# interrupter.net
KiCad netlist of a schematic drawn in EAGLE
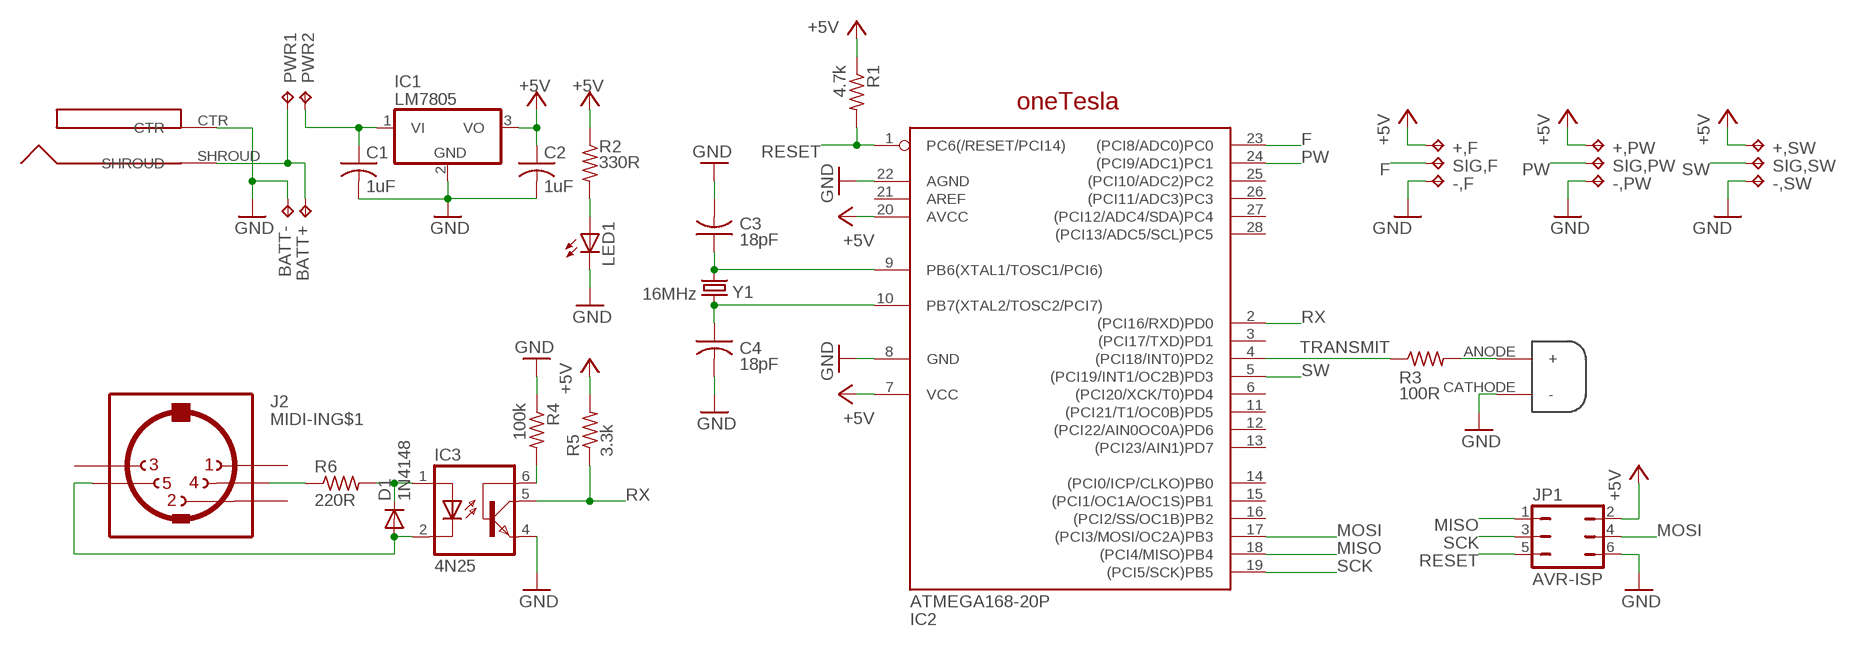
[diagram p0: schematic, sheet 1]

(export (version "E")
  (design (tool "Eeschema 10.0.6"))
  (components
    (comp (ref "+,F")
      (value "TPPAD1-13")
      (footprint "eagle-import:P1-13")
      (libsource (lib "eagle-import") (part "TPPAD1-13"))
    )
    (comp (ref "+,PW")
      (value "TPPAD1-13")
      (footprint "eagle-import:P1-13")
      (libsource (lib "eagle-import") (part "TPPAD1-13"))
    )
    (comp (ref "+,SW")
      (value "TPPAD1-13")
      (footprint "eagle-import:P1-13")
      (libsource (lib "eagle-import") (part "TPPAD1-13"))
    )
    (comp (ref "-,F")
      (value "TPPAD1-13")
      (footprint "eagle-import:P1-13")
      (libsource (lib "eagle-import") (part "TPPAD1-13"))
    )
    (comp (ref "-,PW")
      (value "TPPAD1-13")
      (footprint "eagle-import:P1-13")
      (libsource (lib "eagle-import") (part "TPPAD1-13"))
    )
    (comp (ref "-,SW")
      (value "TPPAD1-13")
      (footprint "eagle-import:P1-13")
      (libsource (lib "eagle-import") (part "TPPAD1-13"))
    )
    (comp (ref "BATT+")
      (value "TPPAD1-13")
      (footprint "eagle-import:P1-13")
      (libsource (lib "eagle-import") (part "TPPAD1-13"))
    )
    (comp (ref "BATT-")
      (value "TPPAD1-13")
      (footprint "eagle-import:P1-13")
      (libsource (lib "eagle-import") (part "TPPAD1-13"))
    )
    (comp (ref "C1")
      (value "1uF")
      (footprint "eagle-import:C050-024X044")
      (libsource (lib "eagle-import") (part "C-US050-024X044"))
    )
    (comp (ref "C2")
      (value "1uF")
      (footprint "eagle-import:C050-024X044")
      (libsource (lib "eagle-import") (part "C-US050-024X044"))
    )
    (comp (ref "C3")
      (value "18pF")
      (footprint "eagle-import:C025-024X044")
      (libsource (lib "eagle-import") (part "C-US025-024X044"))
    )
    (comp (ref "C4")
      (value "18pF")
      (footprint "eagle-import:C025-024X044")
      (libsource (lib "eagle-import") (part "C-US025-024X044"))
    )
    (comp (ref "D1")
      (value "1N4148")
      (footprint "eagle-import:DO35-7")
      (libsource (lib "eagle-import") (part "1N4148DO35-7"))
    )
    (comp (ref "IC1")
      (value "LM7805")
      (footprint "eagle-import:TO220H")
      (libsource (lib "eagle-import") (part "78T05"))
    )
    (comp (ref "IC2")
      (value "ATMEGA168-20P")
      (footprint "eagle-import:DIL28-3")
      (libsource (lib "eagle-import") (part "ATMEGA168P-20"))
    )
    (comp (ref "IC3")
      (value "4N25")
      (footprint "eagle-import:DIL06")
      (fields (field (name "MPN") "4N25-M"))
      (libsource (lib "eagle-import") (part "4N?M25"))
    )
    (comp (ref "JP1")
      (value "AVR-ISP")
      (footprint "eagle-import:JP3Q")
      (libsource (lib "eagle-import") (part "JP3Q"))
    )
    (comp (ref "LED1")
      (value "LED5MM")
      (footprint "eagle-import:LED5MM")
      (libsource (lib "eagle-import") (part "LED5MM"))
    )
    (comp (ref "MIDI-IN")
      (value "J2")
      (footprint "eagle-import:CP-2350")
      (libsource (lib "eagle-import") (part "MIDIJACK"))
    )
    (comp (ref "POWER")
      (value "J1")
      (footprint "eagle-import:DJC0202")
      (libsource (lib "eagle-import") (part "PJ-037B"))
    )
    (comp (ref "PWR1")
      (value "TPPAD1-13")
      (footprint "eagle-import:P1-13")
      (libsource (lib "eagle-import") (part "TPPAD1-13"))
    )
    (comp (ref "PWR2")
      (value "TPPAD1-13")
      (footprint "eagle-import:P1-13")
      (libsource (lib "eagle-import") (part "TPPAD1-13"))
    )
    (comp (ref "R1")
      (value "4.7k")
      (footprint "eagle-import:0207_7")
      (libsource (lib "eagle-import") (part "R-US_0207/7"))
    )
    (comp (ref "R2")
      (value "330R")
      (footprint "eagle-import:0207_7")
      (libsource (lib "eagle-import") (part "R-US_0207/7"))
    )
    (comp (ref "R3")
      (value "100R")
      (footprint "eagle-import:0207_7")
      (libsource (lib "eagle-import") (part "R-US_0207/7"))
    )
    (comp (ref "R4")
      (value "100k")
      (footprint "eagle-import:0207_7")
      (libsource (lib "eagle-import") (part "R-US_0207/7"))
    )
    (comp (ref "R5")
      (value "3.3k")
      (footprint "eagle-import:0207_7")
      (libsource (lib "eagle-import") (part "R-US_0207/7"))
    )
    (comp (ref "R6")
      (value "220R")
      (footprint "eagle-import:0207_7")
      (libsource (lib "eagle-import") (part "R-US_0207/7"))
    )
    (comp (ref "SIG,F")
      (value "TPPAD1-13")
      (footprint "eagle-import:P1-13")
      (libsource (lib "eagle-import") (part "TPPAD1-13"))
    )
    (comp (ref "SIG,PW")
      (value "TPPAD1-13")
      (footprint "eagle-import:P1-13")
      (libsource (lib "eagle-import") (part "TPPAD1-13"))
    )
    (comp (ref "SIG,SW")
      (value "TPPAD1-13")
      (footprint "eagle-import:P1-13")
      (libsource (lib "eagle-import") (part "TPPAD1-13"))
    )
    (comp (ref "U$1")
      (value "LOGO")
      (footprint "eagle-import:LOGO")
      (libsource (lib "eagle-import") (part "LOGO"))
    )
    (comp (ref "U$2")
      (value "IFE96_OPTO")
      (footprint "eagle-import:IFE96")
      (libsource (lib "eagle-import") (part "IFE96_OPTO"))
    )
    (comp (ref "Y1")
      (value "16MHz")
      (footprint "eagle-import:HC49U-V")
      (libsource (lib "eagle-import") (part "CRYSTALHC49UV"))
    )
  )
  (nets
    (net (code "1") (name "+5V") (class "Default")
      (node (ref "+,F") (pin "TP") (pinfunction "TP_TP") (pintype "input"))
      (node (ref "+,PW") (pin "TP") (pinfunction "TP_TP") (pintype "input"))
      (node (ref "+,SW") (pin "TP") (pinfunction "TP_TP") (pintype "input"))
      (node (ref "C2") (pin "1") (pinfunction "1_1") (pintype "passive"))
      (node (ref "IC1") (pin "3") (pinfunction "VO_3") (pintype "passive"))
      (node (ref "IC2") (pin "20") (pinfunction "AVCC_20") (pintype "bidirectional"))
      (node (ref "IC2") (pin "7") (pinfunction "VCC_7") (pintype "bidirectional"))
      (node (ref "JP1") (pin "2") (pinfunction "2_2") (pintype "passive"))
      (node (ref "R1") (pin "1") (pinfunction "1_1") (pintype "passive"))
      (node (ref "R2") (pin "1") (pinfunction "1_1") (pintype "passive"))
      (node (ref "R5") (pin "2") (pinfunction "2_2") (pintype "passive"))
    )
    (net (code "2") (name "/F") (class "Default")
      (node (ref "IC2") (pin "23") (pinfunction "(PCI8/ADC0)PC0_23") (pintype "bidirectional"))
      (node (ref "SIG,F") (pin "TP") (pinfunction "TP_TP") (pintype "input"))
    )
    (net (code "3") (name "/MISO") (class "Default")
      (node (ref "IC2") (pin "18") (pinfunction "(PCI4/MISO)PB4_18") (pintype "bidirectional"))
      (node (ref "JP1") (pin "1") (pinfunction "1_1") (pintype "passive"))
    )
    (net (code "4") (name "/MOSI") (class "Default")
      (node (ref "IC2") (pin "17") (pinfunction "(PCI3/MOSI/OC2A)PB3_17") (pintype "bidirectional"))
      (node (ref "JP1") (pin "4") (pinfunction "4_4") (pintype "passive"))
    )
    (net (code "5") (name "/PW") (class "Default")
      (node (ref "IC2") (pin "24") (pinfunction "(PCI9/ADC1)PC1_24") (pintype "bidirectional"))
      (node (ref "SIG,PW") (pin "TP") (pinfunction "TP_TP") (pintype "input"))
    )
    (net (code "6") (name "/RESET") (class "Default")
      (node (ref "IC2") (pin "1") (pinfunction "PC6(/RESET/PCI14)_1") (pintype "bidirectional"))
      (node (ref "JP1") (pin "5") (pinfunction "5_5") (pintype "passive"))
      (node (ref "R1") (pin "2") (pinfunction "2_2") (pintype "passive"))
    )
    (net (code "7") (name "/RX") (class "Default")
      (node (ref "IC2") (pin "2") (pinfunction "(PCI16/RXD)PD0_2") (pintype "bidirectional"))
      (node (ref "IC3") (pin "5") (pinfunction "COL_5") (pintype "passive"))
      (node (ref "R5") (pin "1") (pinfunction "1_1") (pintype "passive"))
    )
    (net (code "8") (name "/SCK") (class "Default")
      (node (ref "IC2") (pin "19") (pinfunction "(PCI5/SCK)PB5_19") (pintype "bidirectional"))
      (node (ref "JP1") (pin "3") (pinfunction "3_3") (pintype "passive"))
    )
    (net (code "9") (name "/SW") (class "Default")
      (node (ref "IC2") (pin "5") (pinfunction "(PCI19/INT1/OC2B)PD3_5") (pintype "bidirectional"))
      (node (ref "SIG,SW") (pin "TP") (pinfunction "TP_TP") (pintype "input"))
    )
    (net (code "10") (name "/TRANSMIT") (class "Default")
      (node (ref "IC2") (pin "4") (pinfunction "(PCI18/INT0)PD2_4") (pintype "bidirectional"))
      (node (ref "R3") (pin "1") (pinfunction "1_1") (pintype "passive"))
    )
    (net (code "11") (name "GND") (class "Default")
      (node (ref "-,F") (pin "TP") (pinfunction "TP_TP") (pintype "input"))
      (node (ref "-,PW") (pin "TP") (pinfunction "TP_TP") (pintype "input"))
      (node (ref "-,SW") (pin "TP") (pinfunction "TP_TP") (pintype "input"))
      (node (ref "BATT-") (pin "TP") (pinfunction "TP_TP") (pintype "input"))
      (node (ref "C1") (pin "2") (pinfunction "2_2") (pintype "passive"))
      (node (ref "C2") (pin "2") (pinfunction "2_2") (pintype "passive"))
      (node (ref "C3") (pin "2") (pinfunction "2_2") (pintype "passive"))
      (node (ref "C4") (pin "2") (pinfunction "2_2") (pintype "passive"))
      (node (ref "IC1") (pin "2") (pinfunction "GND_2") (pintype "passive"))
      (node (ref "IC2") (pin "22") (pinfunction "AGND_22") (pintype "bidirectional"))
      (node (ref "IC2") (pin "8") (pinfunction "GND_8") (pintype "bidirectional"))
      (node (ref "IC3") (pin "4") (pinfunction "EMI_4") (pintype "passive"))
      (node (ref "JP1") (pin "6") (pinfunction "6_6") (pintype "passive"))
      (node (ref "LED1") (pin "K") (pinfunction "C_K") (pintype "passive"))
      (node (ref "POWER") (pin "CTR") (pinfunction "CTR_CTR") (pintype "bidirectional"))
      (node (ref "R4") (pin "1") (pinfunction "1_1") (pintype "passive"))
      (node (ref "U$2") (pin "CATHODE") (pinfunction "-_CATHODE") (pintype "bidirectional"))
    )
    (net (code "12") (name "Net-(BATT+-PadTP)") (class "Default")
      (node (ref "BATT+") (pin "TP") (pinfunction "TP_TP") (pintype "input"))
      (node (ref "POWER") (pin "SHROUD") (pinfunction "SHROUD_SHROUD") (pintype "bidirectional"))
      (node (ref "PWR1") (pin "TP") (pinfunction "TP_TP") (pintype "input"))
    )
    (net (code "13") (name "Net-(IC1-VI)") (class "Default")
      (node (ref "C1") (pin "1") (pinfunction "1_1") (pintype "passive"))
      (node (ref "IC1") (pin "1") (pinfunction "VI_1") (pintype "input"))
      (node (ref "PWR2") (pin "TP") (pinfunction "TP_TP") (pintype "input"))
    )
    (net (code "14") (name "Net-(IC2-PB6(XTAL1{slash}TOSC1{slash}PCI6))") (class "Default")
      (node (ref "C3") (pin "1") (pinfunction "1_1") (pintype "passive"))
      (node (ref "IC2") (pin "9") (pinfunction "PB6(XTAL1/TOSC1/PCI6)_9") (pintype "bidirectional"))
      (node (ref "Y1") (pin "2") (pinfunction "2_2") (pintype "passive"))
    )
    (net (code "15") (name "Net-(IC2-PB7(XTAL2{slash}TOSC2{slash}PCI7))") (class "Default")
      (node (ref "C4") (pin "1") (pinfunction "1_1") (pintype "passive"))
      (node (ref "IC2") (pin "10") (pinfunction "PB7(XTAL2/TOSC2/PCI7)_10") (pintype "bidirectional"))
      (node (ref "Y1") (pin "1") (pinfunction "1_1") (pintype "passive"))
    )
    (net (code "16") (name "Net-(IC3-A)") (class "Default")
      (node (ref "D1") (pin "C") (pinfunction "C_C") (pintype "passive"))
      (node (ref "IC3") (pin "1") (pinfunction "A_1") (pintype "passive"))
      (node (ref "R6") (pin "2") (pinfunction "2_2") (pintype "passive"))
    )
    (net (code "17") (name "Net-(IC3-BAS)") (class "Default")
      (node (ref "IC3") (pin "6") (pinfunction "BAS_6") (pintype "passive"))
      (node (ref "R4") (pin "2") (pinfunction "2_2") (pintype "passive"))
    )
    (net (code "18") (name "Net-(IC3-C)") (class "Default")
      (node (ref "D1") (pin "A") (pinfunction "A_A") (pintype "passive"))
      (node (ref "IC3") (pin "2") (pinfunction "C_2") (pintype "passive"))
      (node (ref "MIDI-IN") (pin "5") (pinfunction "5_5") (pintype "passive"))
    )
    (net (code "19") (name "Net-(LED1-PadA)") (class "Default")
      (node (ref "LED1") (pin "A") (pinfunction "A_A") (pintype "passive"))
      (node (ref "R2") (pin "2") (pinfunction "2_2") (pintype "passive"))
    )
    (net (code "20") (name "Net-(MIDI-IN-Pad4)") (class "Default")
      (node (ref "MIDI-IN") (pin "4") (pinfunction "4_4") (pintype "passive"))
      (node (ref "R6") (pin "1") (pinfunction "1_1") (pintype "passive"))
    )
    (net (code "21") (name "Net-(U$2-+)") (class "Default")
      (node (ref "R3") (pin "2") (pinfunction "2_2") (pintype "passive"))
      (node (ref "U$2") (pin "ANODE") (pinfunction "+_ANODE") (pintype "bidirectional"))
    )
    (net (code "22") (name "unconnected-(IC2-(PCI0{slash}ICP{slash}CLKO)PB0-Pad14)") (class "Default")
      (node (ref "IC2") (pin "14") (pinfunction "(PCI0/ICP/CLKO)PB0_14") (pintype "bidirectional"))
    )
    (net (code "23") (name "unconnected-(IC2-(PCI1{slash}OC1A{slash}OC1S)PB1-Pad15)") (class "Default")
      (node (ref "IC2") (pin "15") (pinfunction "(PCI1/OC1A/OC1S)PB1_15") (pintype "bidirectional"))
    )
    (net (code "24") (name "unconnected-(IC2-(PCI2{slash}SS{slash}OC1B)PB2-Pad16)") (class "Default")
      (node (ref "IC2") (pin "16") (pinfunction "(PCI2/SS/OC1B)PB2_16") (pintype "bidirectional"))
    )
    (net (code "25") (name "unconnected-(IC2-(PCI10{slash}ADC2)PC2-Pad25)") (class "Default")
      (node (ref "IC2") (pin "25") (pinfunction "(PCI10/ADC2)PC2_25") (pintype "bidirectional"))
    )
    (net (code "26") (name "unconnected-(IC2-(PCI11{slash}ADC3)PC3-Pad26)") (class "Default")
      (node (ref "IC2") (pin "26") (pinfunction "(PCI11/ADC3)PC3_26") (pintype "bidirectional"))
    )
    (net (code "27") (name "unconnected-(IC2-(PCI12{slash}ADC4{slash}SDA)PC4-Pad27)") (class "Default")
      (node (ref "IC2") (pin "27") (pinfunction "(PCI12/ADC4/SDA)PC4_27") (pintype "bidirectional"))
    )
    (net (code "28") (name "unconnected-(IC2-(PCI13{slash}ADC5{slash}SCL)PC5-Pad28)") (class "Default")
      (node (ref "IC2") (pin "28") (pinfunction "(PCI13/ADC5/SCL)PC5_28") (pintype "bidirectional"))
    )
    (net (code "29") (name "unconnected-(IC2-(PCI17{slash}TXD)PD1-Pad3)") (class "Default")
      (node (ref "IC2") (pin "3") (pinfunction "(PCI17/TXD)PD1_3") (pintype "bidirectional"))
    )
    (net (code "30") (name "unconnected-(IC2-(PCI20{slash}XCK{slash}T0)PD4-Pad6)") (class "Default")
      (node (ref "IC2") (pin "6") (pinfunction "(PCI20/XCK/T0)PD4_6") (pintype "bidirectional"))
    )
    (net (code "31") (name "unconnected-(IC2-(PCI21{slash}T1{slash}OC0B)PD5-Pad11)") (class "Default")
      (node (ref "IC2") (pin "11") (pinfunction "(PCI21/T1/OC0B)PD5_11") (pintype "bidirectional"))
    )
    (net (code "32") (name "unconnected-(IC2-(PCI22{slash}AIN0OC0A)PD6-Pad12)") (class "Default")
      (node (ref "IC2") (pin "12") (pinfunction "(PCI22/AIN0OC0A)PD6_12") (pintype "bidirectional"))
    )
    (net (code "33") (name "unconnected-(IC2-(PCI23{slash}AIN1)PD7-Pad13)") (class "Default")
      (node (ref "IC2") (pin "13") (pinfunction "(PCI23/AIN1)PD7_13") (pintype "bidirectional"))
    )
    (net (code "34") (name "unconnected-(IC2-AREF-Pad21)") (class "Default")
      (node (ref "IC2") (pin "21") (pinfunction "AREF_21") (pintype "bidirectional"))
    )
    (net (code "35") (name "unconnected-(MIDI-IN-Pad1)") (class "Default")
      (node (ref "MIDI-IN") (pin "1") (pinfunction "1_1") (pintype "passive"))
    )
    (net (code "36") (name "unconnected-(MIDI-IN-Pad2)") (class "Default")
      (node (ref "MIDI-IN") (pin "2") (pinfunction "2_2") (pintype "passive"))
    )
    (net (code "37") (name "unconnected-(MIDI-IN-Pad3)") (class "Default")
      (node (ref "MIDI-IN") (pin "3") (pinfunction "3_3") (pintype "passive"))
    )
  )
)
